# INKY_PCB.net
KiCad netlist of a schematic drawn in EAGLE
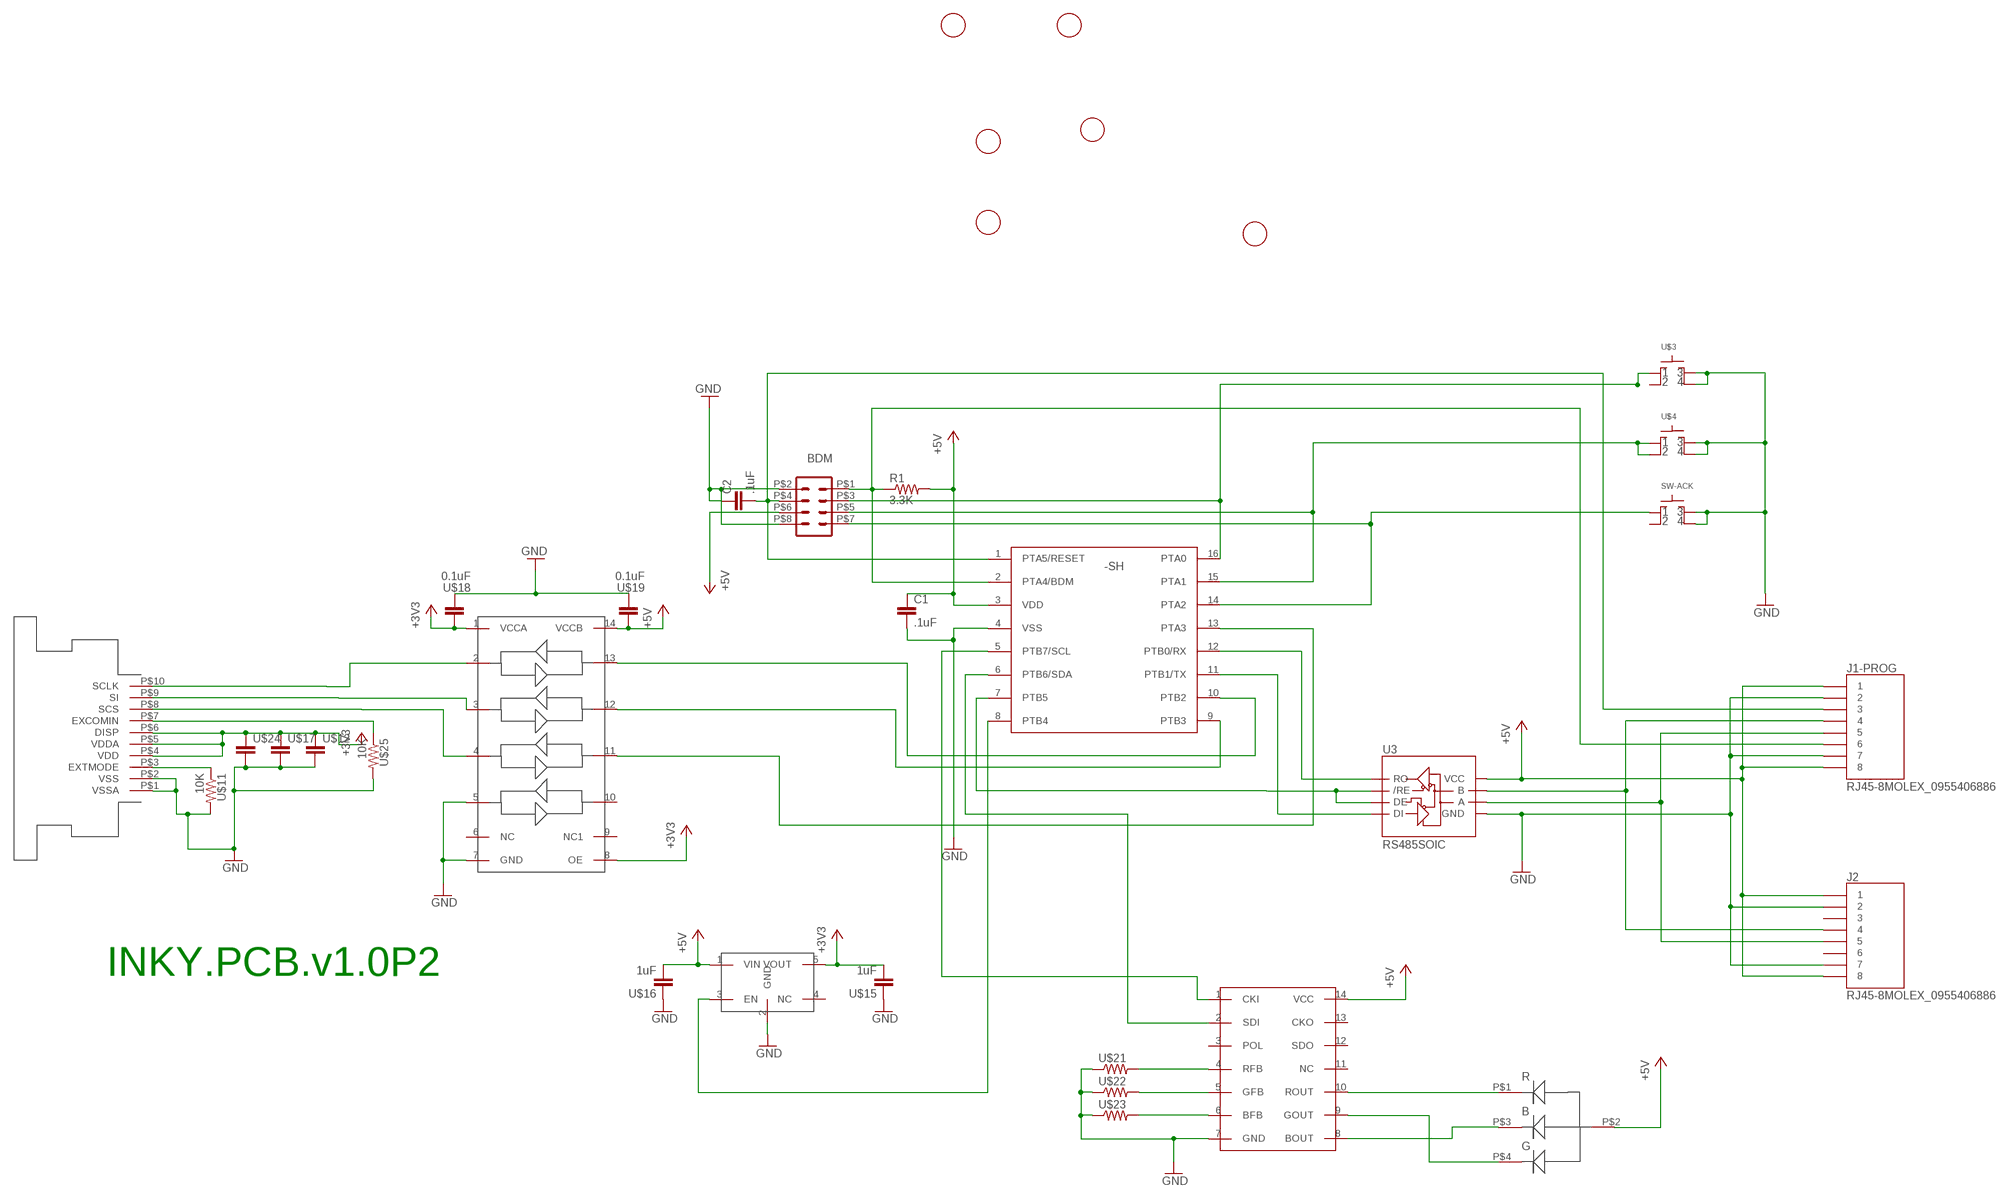
[diagram p0: schematic, sheet 1]

(export (version "E")
  (design (tool "Eeschema 10.0.6"))
  (components
    (comp (ref "BDM")
      (value "TP2X4SMD")
      (footprint "eagle-import:SMD4X2")
      (libsource (lib "eagle-import") (part "TP2X4SMD"))
    )
    (comp (ref "C1")
      (value ".1uF")
      (footprint "eagle-import:C0805")
      (libsource (lib "eagle-import") (part "RF-C0805"))
    )
    (comp (ref "C2")
      (value ".1uF")
      (footprint "eagle-import:C0805")
      (libsource (lib "eagle-import") (part "RF-C0805"))
    )
    (comp (ref "J1-PROG")
      (value "RJ45-8MOLEX_0955406886")
      (footprint "eagle-import:RJ45_GUIDE")
      (libsource (lib "eagle-import") (part "RJ45-8MOLEX_0955406886"))
    )
    (comp (ref "J2")
      (value "RJ45-8MOLEX_0955406886")
      (footprint "eagle-import:RJ45_GUIDE")
      (libsource (lib "eagle-import") (part "RJ45-8MOLEX_0955406886"))
    )
    (comp (ref "R1")
      (value "3.3K")
      (footprint "eagle-import:RF-C0805")
      (libsource (lib "eagle-import") (part "RF-R0805"))
    )
    (comp (ref "SW-ACK")
      (value "SWITCH-TACTILE-5E/5GSH9")
      (footprint "eagle-import:SWITCH_TACTILE-5E_5GSH9")
      (libsource (lib "eagle-import") (part "SWITCH-TACTILE-5E/5GSH9"))
    )
    (comp (ref "U$1")
      (value "FIDUCIAL")
      (footprint "eagle-import:FIDUCIAL_1MM")
      (libsource (lib "eagle-import") (part "FIDUCIAL"))
    )
    (comp (ref "U$2")
      (value "FIDUCIAL")
      (footprint "eagle-import:FIDUCIAL_1MM")
      (libsource (lib "eagle-import") (part "FIDUCIAL"))
    )
    (comp (ref "U$3")
      (value "SWITCH-TACTILE")
      (footprint "eagle-import:ESWITCH-TL3301PF")
      (libsource (lib "eagle-import") (part "SWITCH-TACTILE"))
    )
    (comp (ref "U$4")
      (value "SWITCH-TACTILE")
      (footprint "eagle-import:ESWITCH-TL3301PF")
      (libsource (lib "eagle-import") (part "SWITCH-TACTILE"))
    )
    (comp (ref "U$5")
      (value "WS2801")
      (footprint "eagle-import:SO14")
      (libsource (lib "eagle-import") (part "WS2801"))
    )
    (comp (ref "U$6")
      (value "FIDUCIAL")
      (footprint "eagle-import:FIDUCIAL_1MM")
      (libsource (lib "eagle-import") (part "FIDUCIAL"))
    )
    (comp (ref "U$7")
      (value "FIDUCIAL")
      (footprint "eagle-import:FIDUCIAL_1MM")
      (libsource (lib "eagle-import") (part "FIDUCIAL"))
    )
    (comp (ref "U$8")
      (value "FIDUCIAL")
      (footprint "eagle-import:FIDUCIAL_1MM")
      (libsource (lib "eagle-import") (part "FIDUCIAL"))
    )
    (comp (ref "U$9")
      (value "FIDUCIAL")
      (footprint "eagle-import:FIDUCIAL_1MM")
      (libsource (lib "eagle-import") (part "FIDUCIAL"))
    )
    (comp (ref "U$10")
      (value "52745-1097")
      (footprint "eagle-import:FPC")
      (fields (field (name "MFGP") "52745-1097"))
      (libsource (lib "eagle-import") (part "52745-1097"))
    )
    (comp (ref "U$11")
      (value "10K")
      (footprint "eagle-import:RF-C0805")
      (libsource (lib "eagle-import") (part "RF-R0805"))
    )
    (comp (ref "U$12")
      (value "RF-C0805")
      (footprint "eagle-import:C0805")
      (libsource (lib "eagle-import") (part "RF-C0805"))
    )
    (comp (ref "U$13")
      (value "AAT3221IGV-3.3-T1")
      (footprint "eagle-import:SOT23-5")
      (libsource (lib "eagle-import") (part "AAT3221IGV-3.3-T1"))
    )
    (comp (ref "U$14")
      (value "TXB0104")
      (footprint "eagle-import:PW_R-PDSO-G14")
      (libsource (lib "eagle-import") (part "TXB0104"))
    )
    (comp (ref "U$15")
      (value "1uF")
      (footprint "eagle-import:C0805")
      (libsource (lib "eagle-import") (part "RF-C0805"))
    )
    (comp (ref "U$16")
      (value "1uF")
      (footprint "eagle-import:C0805")
      (libsource (lib "eagle-import") (part "RF-C0805"))
    )
    (comp (ref "U$17")
      (value "RF-C0805")
      (footprint "eagle-import:C0805")
      (libsource (lib "eagle-import") (part "RF-C0805"))
    )
    (comp (ref "U$18")
      (value "0.1uF")
      (footprint "eagle-import:C0805")
      (libsource (lib "eagle-import") (part "RF-C0805"))
    )
    (comp (ref "U$19")
      (value "0.1uF")
      (footprint "eagle-import:C0805")
      (libsource (lib "eagle-import") (part "RF-C0805"))
    )
    (comp (ref "U$20")
      (value "RGLBED")
      (footprint "eagle-import:PLCC4_SMALL")
      (libsource (lib "eagle-import") (part "RGLBED"))
    )
    (comp (ref "U$21")
      (value "RF-R0805")
      (footprint "eagle-import:RF-C0805")
      (libsource (lib "eagle-import") (part "RF-R0805"))
    )
    (comp (ref "U$22")
      (value "RF-R0805")
      (footprint "eagle-import:RF-C0805")
      (libsource (lib "eagle-import") (part "RF-R0805"))
    )
    (comp (ref "U$23")
      (value "RF-R0805")
      (footprint "eagle-import:RF-C0805")
      (libsource (lib "eagle-import") (part "RF-R0805"))
    )
    (comp (ref "U$24")
      (value "RF-C0805")
      (footprint "eagle-import:C0805")
      (libsource (lib "eagle-import") (part "RF-C0805"))
    )
    (comp (ref "U$25")
      (value "10K")
      (footprint "eagle-import:RF-C0805")
      (libsource (lib "eagle-import") (part "RF-R0805"))
    )
    (comp (ref "U1")
      (value "MC9S08SH8CTG")
      (footprint "eagle-import:TSSOP16")
      (libsource (lib "eagle-import") (part "MC9S08SH8CTG"))
    )
    (comp (ref "U3")
      (value "RS485SOIC")
      (footprint "eagle-import:SO08")
      (fields (field (name "MFGP") "SN65HVD1781DR"))
      (libsource (lib "eagle-import") (part "RS485SOIC"))
    )
  )
  (nets
    (net (code "1") (name "+3V3") (class "Default")
      (node (ref "U$10") (pin "P$4") (pinfunction "VDD_P$4") (pintype "bidirectional"))
      (node (ref "U$10") (pin "P$5") (pinfunction "VDDA_P$5") (pintype "bidirectional"))
      (node (ref "U$10") (pin "P$6") (pinfunction "DISP_P$6") (pintype "bidirectional"))
      (node (ref "U$12") (pin "1") (pinfunction "1_1") (pintype "passive"))
      (node (ref "U$13") (pin "5") (pinfunction "VOUT_5") (pintype "bidirectional"))
      (node (ref "U$14") (pin "1") (pinfunction "VCCA_1") (pintype "bidirectional"))
      (node (ref "U$14") (pin "8") (pinfunction "OE_8") (pintype "bidirectional"))
      (node (ref "U$15") (pin "2") (pinfunction "2_2") (pintype "passive"))
      (node (ref "U$17") (pin "1") (pinfunction "1_1") (pintype "passive"))
      (node (ref "U$18") (pin "1") (pinfunction "1_1") (pintype "passive"))
      (node (ref "U$24") (pin "1") (pinfunction "1_1") (pintype "passive"))
    )
    (net (code "2") (name "+5V") (class "Default")
      (node (ref "BDM") (pin "P$6") (pinfunction "6_P$6") (pintype "passive"))
      (node (ref "C1") (pin "1") (pinfunction "1_1") (pintype "passive"))
      (node (ref "J1-PROG") (pin "P$1") (pinfunction "1_P$1") (pintype "bidirectional"))
      (node (ref "J1-PROG") (pin "P$8") (pinfunction "8_P$8") (pintype "bidirectional"))
      (node (ref "J2") (pin "P$1") (pinfunction "1_P$1") (pintype "bidirectional"))
      (node (ref "J2") (pin "P$8") (pinfunction "8_P$8") (pintype "bidirectional"))
      (node (ref "R1") (pin "2") (pinfunction "2_2") (pintype "passive"))
      (node (ref "U$13") (pin "1") (pinfunction "VIN_1") (pintype "bidirectional"))
      (node (ref "U$14") (pin "14") (pinfunction "VCCB_14") (pintype "bidirectional"))
      (node (ref "U$16") (pin "2") (pinfunction "2_2") (pintype "passive"))
      (node (ref "U$19") (pin "1") (pinfunction "1_1") (pintype "passive"))
      (node (ref "U$20") (pin "P$2") (pinfunction "ANODE_P$2") (pintype "bidirectional"))
      (node (ref "U$5") (pin "14") (pinfunction "VCC_14") (pintype "bidirectional"))
      (node (ref "U1") (pin "3") (pinfunction "VDD_3") (pintype "bidirectional"))
      (node (ref "U3") (pin "8") (pinfunction "VCC_8") (pintype "bidirectional"))
    )
    (net (code "3") (name "GND") (class "Default")
      (node (ref "BDM") (pin "P$2") (pinfunction "2_P$2") (pintype "passive"))
      (node (ref "BDM") (pin "P$8") (pinfunction "8_P$8") (pintype "passive"))
      (node (ref "C1") (pin "2") (pinfunction "2_2") (pintype "passive"))
      (node (ref "C2") (pin "1") (pinfunction "1_1") (pintype "passive"))
      (node (ref "J1-PROG") (pin "P$2") (pinfunction "2_P$2") (pintype "bidirectional"))
      (node (ref "J1-PROG") (pin "P$7") (pinfunction "7_P$7") (pintype "bidirectional"))
      (node (ref "J2") (pin "P$2") (pinfunction "2_P$2") (pintype "bidirectional"))
      (node (ref "J2") (pin "P$7") (pinfunction "7_P$7") (pintype "bidirectional"))
      (node (ref "SW-ACK") (pin "P$3") (pinfunction "3_P$3") (pintype "input"))
      (node (ref "SW-ACK") (pin "P$4") (pinfunction "4_P$4") (pintype "input"))
      (node (ref "U$10") (pin "P$1") (pinfunction "VSSA_P$1") (pintype "bidirectional"))
      (node (ref "U$10") (pin "P$2") (pinfunction "VSS_P$2") (pintype "bidirectional"))
      (node (ref "U$11") (pin "2") (pinfunction "2_2") (pintype "passive"))
      (node (ref "U$12") (pin "2") (pinfunction "2_2") (pintype "passive"))
      (node (ref "U$13") (pin "2") (pinfunction "GND_2") (pintype "bidirectional"))
      (node (ref "U$14") (pin "5") (pinfunction "P$5_5") (pintype "bidirectional"))
      (node (ref "U$14") (pin "7") (pinfunction "GND_7") (pintype "bidirectional"))
      (node (ref "U$15") (pin "1") (pinfunction "1_1") (pintype "passive"))
      (node (ref "U$16") (pin "1") (pinfunction "1_1") (pintype "passive"))
      (node (ref "U$17") (pin "2") (pinfunction "2_2") (pintype "passive"))
      (node (ref "U$18") (pin "2") (pinfunction "2_2") (pintype "passive"))
      (node (ref "U$19") (pin "2") (pinfunction "2_2") (pintype "passive"))
      (node (ref "U$21") (pin "1") (pinfunction "1_1") (pintype "passive"))
      (node (ref "U$22") (pin "1") (pinfunction "1_1") (pintype "passive"))
      (node (ref "U$23") (pin "1") (pinfunction "1_1") (pintype "passive"))
      (node (ref "U$24") (pin "2") (pinfunction "2_2") (pintype "passive"))
      (node (ref "U$25") (pin "2") (pinfunction "2_2") (pintype "passive"))
      (node (ref "U$3") (pin "3") (pinfunction "3_3") (pintype "input"))
      (node (ref "U$3") (pin "4") (pinfunction "4_4") (pintype "input"))
      (node (ref "U$4") (pin "3") (pinfunction "3_3") (pintype "input"))
      (node (ref "U$4") (pin "4") (pinfunction "4_4") (pintype "input"))
      (node (ref "U$5") (pin "7") (pinfunction "GND_7") (pintype "bidirectional"))
      (node (ref "U1") (pin "4") (pinfunction "VSS_4") (pintype "bidirectional"))
      (node (ref "U3") (pin "5") (pinfunction "GND_5") (pintype "bidirectional"))
    )
    (net (code "4") (name "Net-(BDM-1)") (class "Default")
      (node (ref "BDM") (pin "P$1") (pinfunction "1_P$1") (pintype "passive"))
      (node (ref "J1-PROG") (pin "P$6") (pinfunction "6_P$6") (pintype "bidirectional"))
      (node (ref "R1") (pin "1") (pinfunction "1_1") (pintype "passive"))
      (node (ref "U1") (pin "2") (pinfunction "PTA4/BDM_2") (pintype "bidirectional"))
    )
    (net (code "5") (name "Net-(BDM-3)") (class "Default")
      (node (ref "BDM") (pin "P$3") (pinfunction "3_P$3") (pintype "passive"))
      (node (ref "U$3") (pin "1") (pinfunction "1_1") (pintype "input"))
      (node (ref "U1") (pin "16") (pinfunction "PTA0_16") (pintype "bidirectional"))
    )
    (net (code "6") (name "Net-(BDM-4)") (class "Default")
      (node (ref "BDM") (pin "P$4") (pinfunction "4_P$4") (pintype "passive"))
      (node (ref "C2") (pin "2") (pinfunction "2_2") (pintype "passive"))
      (node (ref "J1-PROG") (pin "P$3") (pinfunction "3_P$3") (pintype "bidirectional"))
      (node (ref "U1") (pin "1") (pinfunction "PTA5/RESET_1") (pintype "bidirectional"))
    )
    (net (code "7") (name "Net-(BDM-5)") (class "Default")
      (node (ref "BDM") (pin "P$5") (pinfunction "5_P$5") (pintype "passive"))
      (node (ref "U$4") (pin "1") (pinfunction "1_1") (pintype "input"))
      (node (ref "U$4") (pin "2") (pinfunction "2_2") (pintype "input"))
      (node (ref "U1") (pin "15") (pinfunction "PTA1_15") (pintype "bidirectional"))
    )
    (net (code "8") (name "Net-(BDM-7)") (class "Default")
      (node (ref "BDM") (pin "P$7") (pinfunction "7_P$7") (pintype "passive"))
      (node (ref "SW-ACK") (pin "P$1") (pinfunction "1_P$1") (pintype "input"))
      (node (ref "U1") (pin "14") (pinfunction "PTA2_14") (pintype "bidirectional"))
    )
    (net (code "9") (name "Net-(J1-PROG-4)") (class "Default")
      (node (ref "J1-PROG") (pin "P$4") (pinfunction "4_P$4") (pintype "bidirectional"))
      (node (ref "J2") (pin "P$4") (pinfunction "4_P$4") (pintype "bidirectional"))
      (node (ref "U3") (pin "7") (pinfunction "B_7") (pintype "bidirectional"))
    )
    (net (code "10") (name "Net-(J1-PROG-5)") (class "Default")
      (node (ref "J1-PROG") (pin "P$5") (pinfunction "5_P$5") (pintype "bidirectional"))
      (node (ref "J2") (pin "P$5") (pinfunction "5_P$5") (pintype "bidirectional"))
      (node (ref "U3") (pin "6") (pinfunction "A_6") (pintype "bidirectional"))
    )
    (net (code "11") (name "Net-(U$5-BFB)") (class "Default")
      (node (ref "U$23") (pin "2") (pinfunction "2_2") (pintype "passive"))
      (node (ref "U$5") (pin "6") (pinfunction "BFB_6") (pintype "bidirectional"))
    )
    (net (code "12") (name "Net-(U$5-CKI)") (class "Default")
      (node (ref "U$5") (pin "1") (pinfunction "CKI_1") (pintype "bidirectional"))
      (node (ref "U1") (pin "5") (pinfunction "PTB7/SCL_5") (pintype "bidirectional"))
    )
    (net (code "13") (name "Net-(U$5-GFB)") (class "Default")
      (node (ref "U$22") (pin "2") (pinfunction "2_2") (pintype "passive"))
      (node (ref "U$5") (pin "5") (pinfunction "GFB_5") (pintype "bidirectional"))
    )
    (net (code "14") (name "Net-(U$5-RFB)") (class "Default")
      (node (ref "U$21") (pin "2") (pinfunction "2_2") (pintype "passive"))
      (node (ref "U$5") (pin "4") (pinfunction "RFB_4") (pintype "bidirectional"))
    )
    (net (code "15") (name "Net-(U$5-SDI)") (class "Default")
      (node (ref "U$5") (pin "2") (pinfunction "SDI_2") (pintype "bidirectional"))
      (node (ref "U1") (pin "6") (pinfunction "PTB6/SDA_6") (pintype "bidirectional"))
    )
    (net (code "16") (name "Net-(U$10-EXCOMIN)") (class "Default")
      (node (ref "U$10") (pin "P$7") (pinfunction "EXCOMIN_P$7") (pintype "bidirectional"))
      (node (ref "U$25") (pin "1") (pinfunction "1_1") (pintype "passive"))
    )
    (net (code "17") (name "Net-(U$10-EXTMODE)") (class "Default")
      (node (ref "U$10") (pin "P$3") (pinfunction "EXTMODE_P$3") (pintype "bidirectional"))
      (node (ref "U$11") (pin "1") (pinfunction "1_1") (pintype "passive"))
    )
    (net (code "18") (name "Net-(U$10-SCLK)") (class "Default")
      (node (ref "U$10") (pin "P$10") (pinfunction "SCLK_P$10") (pintype "bidirectional"))
      (node (ref "U$14") (pin "2") (pinfunction "P$2_2") (pintype "bidirectional"))
    )
    (net (code "19") (name "Net-(U$10-SCS)") (class "Default")
      (node (ref "U$10") (pin "P$8") (pinfunction "SCS_P$8") (pintype "bidirectional"))
      (node (ref "U$14") (pin "4") (pinfunction "P$4_4") (pintype "bidirectional"))
    )
    (net (code "20") (name "Net-(U$10-SI)") (class "Default")
      (node (ref "U$10") (pin "P$9") (pinfunction "SI_P$9") (pintype "bidirectional"))
      (node (ref "U$14") (pin "3") (pinfunction "P$3_3") (pintype "bidirectional"))
    )
    (net (code "21") (name "Net-(U$13-EN)") (class "Default")
      (node (ref "U$13") (pin "3") (pinfunction "EN_3") (pintype "bidirectional"))
      (node (ref "U1") (pin "8") (pinfunction "PTB4_8") (pintype "bidirectional"))
    )
    (net (code "22") (name "Net-(U$14-P$11)") (class "Default")
      (node (ref "U$14") (pin "11") (pinfunction "P$11_11") (pintype "bidirectional"))
      (node (ref "U1") (pin "13") (pinfunction "PTA3_13") (pintype "bidirectional"))
    )
    (net (code "23") (name "Net-(U$14-P$12)") (class "Default")
      (node (ref "U$14") (pin "12") (pinfunction "P$12_12") (pintype "bidirectional"))
      (node (ref "U1") (pin "9") (pinfunction "PTB3_9") (pintype "bidirectional"))
    )
    (net (code "24") (name "Net-(U$14-P$13)") (class "Default")
      (node (ref "U$14") (pin "13") (pinfunction "P$13_13") (pintype "bidirectional"))
      (node (ref "U1") (pin "10") (pinfunction "PTB2_10") (pintype "bidirectional"))
    )
    (net (code "25") (name "Net-(U$20-BLUE)") (class "Default")
      (node (ref "U$20") (pin "P$3") (pinfunction "BLUE_P$3") (pintype "bidirectional"))
      (node (ref "U$5") (pin "8") (pinfunction "BOUT_8") (pintype "bidirectional"))
    )
    (net (code "26") (name "Net-(U$20-GREEN)") (class "Default")
      (node (ref "U$20") (pin "P$4") (pinfunction "GREEN_P$4") (pintype "bidirectional"))
      (node (ref "U$5") (pin "9") (pinfunction "GOUT_9") (pintype "bidirectional"))
    )
    (net (code "27") (name "Net-(U$20-RED)") (class "Default")
      (node (ref "U$20") (pin "P$1") (pinfunction "RED_P$1") (pintype "bidirectional"))
      (node (ref "U$5") (pin "10") (pinfunction "ROUT_10") (pintype "bidirectional"))
    )
    (net (code "28") (name "Net-(U1-PTB0{slash}RX)") (class "Default")
      (node (ref "U1") (pin "12") (pinfunction "PTB0/RX_12") (pintype "bidirectional"))
      (node (ref "U3") (pin "1") (pinfunction "RO_1") (pintype "bidirectional"))
    )
    (net (code "29") (name "Net-(U1-PTB1{slash}TX)") (class "Default")
      (node (ref "U1") (pin "11") (pinfunction "PTB1/TX_11") (pintype "bidirectional"))
      (node (ref "U3") (pin "4") (pinfunction "DI_4") (pintype "bidirectional"))
    )
    (net (code "30") (name "Net-(U1-PTB5)") (class "Default")
      (node (ref "U1") (pin "7") (pinfunction "PTB5_7") (pintype "bidirectional"))
      (node (ref "U3") (pin "2") (pinfunction "/RE_2") (pintype "bidirectional"))
      (node (ref "U3") (pin "3") (pinfunction "DE_3") (pintype "bidirectional"))
    )
    (net (code "31") (name "unconnected-(J2-3-PadP$3)") (class "Default")
      (node (ref "J2") (pin "P$3") (pinfunction "3_P$3") (pintype "bidirectional"))
    )
    (net (code "32") (name "unconnected-(J2-6-PadP$6)") (class "Default")
      (node (ref "J2") (pin "P$6") (pinfunction "6_P$6") (pintype "bidirectional"))
    )
    (net (code "33") (name "unconnected-(SW-ACK-2-PadP$2)") (class "Default")
      (node (ref "SW-ACK") (pin "P$2") (pinfunction "2_P$2") (pintype "input"))
    )
    (net (code "34") (name "unconnected-(U$3-Pad2)") (class "Default")
      (node (ref "U$3") (pin "2") (pinfunction "2_2") (pintype "input"))
    )
    (net (code "35") (name "unconnected-(U$5-CKO-Pad13)") (class "Default")
      (node (ref "U$5") (pin "13") (pinfunction "CKO_13") (pintype "bidirectional"))
    )
    (net (code "36") (name "unconnected-(U$5-NC-Pad11)") (class "Default")
      (node (ref "U$5") (pin "11") (pinfunction "NC_11") (pintype "bidirectional"))
    )
    (net (code "37") (name "unconnected-(U$5-POL-Pad3)") (class "Default")
      (node (ref "U$5") (pin "3") (pinfunction "POL_3") (pintype "bidirectional"))
    )
    (net (code "38") (name "unconnected-(U$5-SDO-Pad12)") (class "Default")
      (node (ref "U$5") (pin "12") (pinfunction "SDO_12") (pintype "bidirectional"))
    )
    (net (code "39") (name "unconnected-(U$13-NC-Pad4)") (class "Default")
      (node (ref "U$13") (pin "4") (pinfunction "NC_4") (pintype "no_connect"))
    )
    (net (code "40") (name "unconnected-(U$14-NC-Pad6)") (class "Default")
      (node (ref "U$14") (pin "6") (pinfunction "NC_6") (pintype "bidirectional"))
    )
    (net (code "41") (name "unconnected-(U$14-NC1-Pad9)") (class "Default")
      (node (ref "U$14") (pin "9") (pinfunction "NC1_9") (pintype "bidirectional"))
    )
    (net (code "42") (name "unconnected-(U$14-P$10-Pad10)") (class "Default")
      (node (ref "U$14") (pin "10") (pinfunction "P$10_10") (pintype "bidirectional"))
    )
  )
)
